# 11_LMS1_Power.net
KiCad netlist of a schematic drawn in Altium Designer
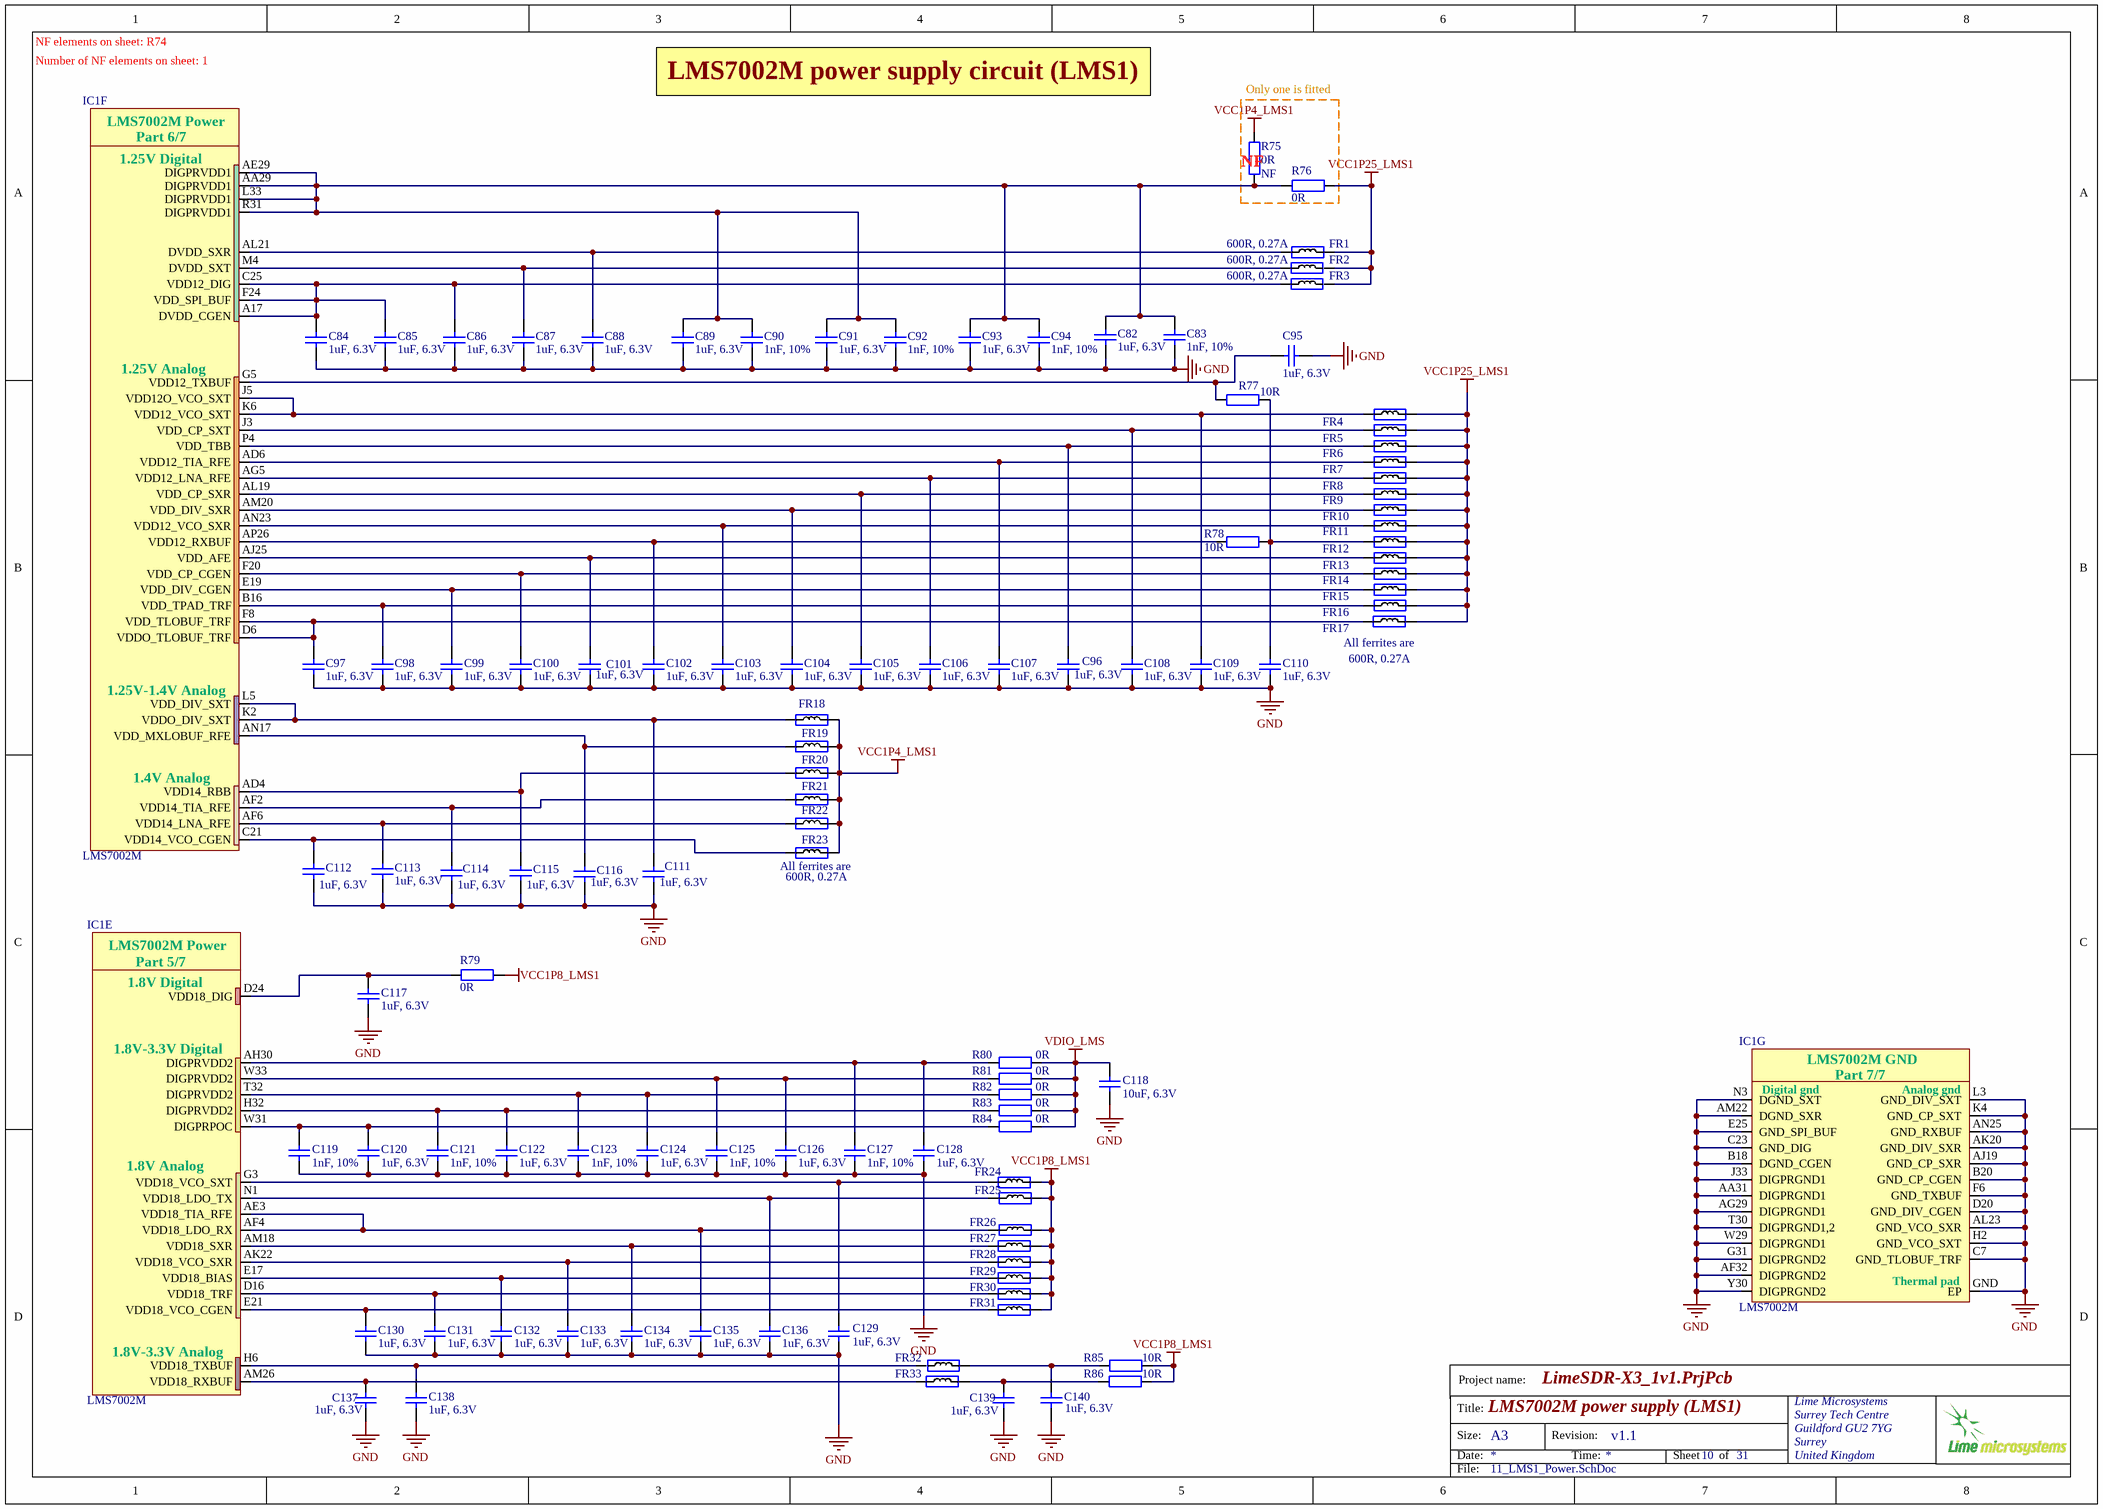
[diagram p0: 11_LMS1_Power.SchDoc]

(export (version "E")
  (design (tool "Eeschema 10.0.6"))
  (components
    (comp (ref "C82")
      (value "1uF, 6.3V")
      (footprint "CAP0201")
      (fields (field (name "TOLERANCE") "±20%") (field (name "MANUFACTURER") "TDK Corporation"))
      (libsource (lib "LimeMicroAltiumLib_schLib") (part "Cap_0402"))
    )
    (comp (ref "C83")
      (value "1nF, 10%")
      (footprint "CAP0201")
      (fields (field (name "TOLERANCE") "±10%") (field (name "MANUFACTURER") "TDK Corporation"))
      (libsource (lib "LimeMicroAltiumLib_schLib") (part "Cap_0402"))
    )
    (comp (ref "C84")
      (value "1uF, 6.3V")
      (footprint "CAP0201")
      (fields (field (name "TOLERANCE") "±20%") (field (name "MANUFACTURER") "TDK Corporation"))
      (libsource (lib "") (part "Cap_0402_1"))
    )
    (comp (ref "C85")
      (value "1uF, 6.3V")
      (footprint "CAP0201")
      (fields (field (name "TOLERANCE") "±20%") (field (name "MANUFACTURER") "TDK Corporation"))
      (libsource (lib "") (part "Cap_0402_1"))
    )
    (comp (ref "C86")
      (value "1uF, 6.3V")
      (footprint "CAP0201")
      (fields (field (name "TOLERANCE") "±20%") (field (name "MANUFACTURER") "TDK Corporation"))
      (libsource (lib "") (part "Cap_0402_1"))
    )
    (comp (ref "C87")
      (value "1uF, 6.3V")
      (footprint "CAP0201")
      (fields (field (name "TOLERANCE") "±20%") (field (name "MANUFACTURER") "TDK Corporation"))
      (libsource (lib "LimeMicroAltiumLib_schLib") (part "Cap_0402"))
    )
    (comp (ref "C88")
      (value "1uF, 6.3V")
      (footprint "CAP0201")
      (fields (field (name "TOLERANCE") "±20%") (field (name "MANUFACTURER") "TDK Corporation"))
      (libsource (lib "") (part "Cap_0402_1"))
    )
    (comp (ref "C89")
      (value "1uF, 6.3V")
      (footprint "CAP0201")
      (fields (field (name "TOLERANCE") "±20%") (field (name "MANUFACTURER") "TDK Corporation"))
      (libsource (lib "LimeMicroAltiumLib_schLib") (part "Cap_0402"))
    )
    (comp (ref "C90")
      (value "1nF, 10%")
      (footprint "CAP0201")
      (fields (field (name "TOLERANCE") "±10%") (field (name "MANUFACTURER") "TDK Corporation"))
      (libsource (lib "LimeMicroAltiumLib_schLib") (part "Cap_0402"))
    )
    (comp (ref "C91")
      (value "1uF, 6.3V")
      (footprint "CAP0201")
      (fields (field (name "TOLERANCE") "±20%") (field (name "MANUFACTURER") "TDK Corporation"))
      (libsource (lib "LimeMicroAltiumLib_schLib") (part "Cap_0402"))
    )
    (comp (ref "C92")
      (value "1nF, 10%")
      (footprint "CAP0201")
      (fields (field (name "TOLERANCE") "±10%") (field (name "MANUFACTURER") "TDK Corporation"))
      (libsource (lib "LimeMicroAltiumLib_schLib") (part "Cap_0402"))
    )
    (comp (ref "C93")
      (value "1uF, 6.3V")
      (footprint "CAP0201")
      (fields (field (name "TOLERANCE") "±20%") (field (name "MANUFACTURER") "TDK Corporation"))
      (libsource (lib "LimeMicroAltiumLib_schLib") (part "Cap_0402"))
    )
    (comp (ref "C94")
      (value "1nF, 10%")
      (footprint "CAP0201")
      (fields (field (name "TOLERANCE") "±10%") (field (name "MANUFACTURER") "TDK Corporation"))
      (libsource (lib "LimeMicroAltiumLib_schLib") (part "Cap_0402"))
    )
    (comp (ref "C95")
      (value "1uF, 6.3V")
      (footprint "CAP0201")
      (fields (field (name "TOLERANCE") "±20%") (field (name "MANUFACTURER") "TDK Corporation"))
      (libsource (lib "") (part "Cap_0402_4"))
    )
    (comp (ref "C96")
      (value "1uF, 6.3V")
      (footprint "CAP0201")
      (fields (field (name "TOLERANCE") "±20%") (field (name "MANUFACTURER") "TDK Corporation"))
      (libsource (lib "") (part "Cap_0402_1"))
    )
    (comp (ref "C97")
      (value "1uF, 6.3V")
      (footprint "CAP0201")
      (fields (field (name "TOLERANCE") "±20%") (field (name "MANUFACTURER") "TDK Corporation"))
      (libsource (lib "") (part "Cap_0402_1"))
    )
    (comp (ref "C98")
      (value "1uF, 6.3V")
      (footprint "CAP0201")
      (fields (field (name "TOLERANCE") "±20%") (field (name "MANUFACTURER") "TDK Corporation"))
      (libsource (lib "") (part "Cap_0402_1"))
    )
    (comp (ref "C99")
      (value "1uF, 6.3V")
      (footprint "CAP0201")
      (fields (field (name "TOLERANCE") "±20%") (field (name "MANUFACTURER") "TDK Corporation"))
      (libsource (lib "") (part "Cap_0402_1"))
    )
    (comp (ref "C100")
      (value "1uF, 6.3V")
      (footprint "CAP0201")
      (fields (field (name "TOLERANCE") "±20%") (field (name "MANUFACTURER") "TDK Corporation"))
      (libsource (lib "LimeMicroAltiumLib_schLib") (part "Cap_0402"))
    )
    (comp (ref "C101")
      (value "1uF, 6.3V")
      (footprint "CAP0201")
      (fields (field (name "TOLERANCE") "±20%") (field (name "MANUFACTURER") "TDK Corporation"))
      (libsource (lib "") (part "Cap_0402_1"))
    )
    (comp (ref "C102")
      (value "1uF, 6.3V")
      (footprint "CAP0201")
      (fields (field (name "TOLERANCE") "±20%") (field (name "MANUFACTURER") "TDK Corporation"))
      (libsource (lib "") (part "Cap_0402_1"))
    )
    (comp (ref "C103")
      (value "1uF, 6.3V")
      (footprint "CAP0201")
      (fields (field (name "TOLERANCE") "±20%") (field (name "MANUFACTURER") "TDK Corporation"))
      (libsource (lib "") (part "Cap_0402_1"))
    )
    (comp (ref "C104")
      (value "1uF, 6.3V")
      (footprint "CAP0201")
      (fields (field (name "TOLERANCE") "±20%") (field (name "MANUFACTURER") "TDK Corporation"))
      (libsource (lib "") (part "Cap_0402_1"))
    )
    (comp (ref "C105")
      (value "1uF, 6.3V")
      (footprint "CAP0201")
      (fields (field (name "TOLERANCE") "±20%") (field (name "MANUFACTURER") "TDK Corporation"))
      (libsource (lib "") (part "Cap_0402_1"))
    )
    (comp (ref "C106")
      (value "1uF, 6.3V")
      (footprint "CAP0201")
      (fields (field (name "TOLERANCE") "±20%") (field (name "MANUFACTURER") "TDK Corporation"))
      (libsource (lib "") (part "Cap_0402_1"))
    )
    (comp (ref "C107")
      (value "1uF, 6.3V")
      (footprint "CAP0201")
      (fields (field (name "TOLERANCE") "±20%") (field (name "MANUFACTURER") "TDK Corporation"))
      (libsource (lib "LimeMicroAltiumLib_schLib") (part "Cap_0402"))
    )
    (comp (ref "C108")
      (value "1uF, 6.3V")
      (footprint "CAP0201")
      (fields (field (name "TOLERANCE") "±20%") (field (name "MANUFACTURER") "TDK Corporation"))
      (libsource (lib "") (part "Cap_0402_1"))
    )
    (comp (ref "C109")
      (value "1uF, 6.3V")
      (footprint "CAP0201")
      (fields (field (name "TOLERANCE") "±20%") (field (name "MANUFACTURER") "TDK Corporation"))
      (libsource (lib "LimeMicroAltiumLib_schLib") (part "Cap_0402"))
    )
    (comp (ref "C110")
      (value "1uF, 6.3V")
      (footprint "CAP0201")
      (fields (field (name "TOLERANCE") "±20%") (field (name "MANUFACTURER") "TDK Corporation"))
      (libsource (lib "LimeMicroAltiumLib_schLib") (part "Cap_0402"))
    )
    (comp (ref "C111")
      (value "1uF, 6.3V")
      (footprint "CAP0201")
      (fields (field (name "TOLERANCE") "±20%") (field (name "MANUFACTURER") "TDK Corporation"))
      (libsource (lib "") (part "Cap_0402_1"))
    )
    (comp (ref "C112")
      (value "1uF, 6.3V")
      (footprint "CAP0201")
      (fields (field (name "TOLERANCE") "±20%") (field (name "MANUFACTURER") "TDK Corporation"))
      (libsource (lib "") (part "Cap_0402_1"))
    )
    (comp (ref "C113")
      (value "1uF, 6.3V")
      (footprint "CAP0201")
      (fields (field (name "TOLERANCE") "±20%") (field (name "MANUFACTURER") "TDK Corporation"))
      (libsource (lib "") (part "Cap_0402_1"))
    )
    (comp (ref "C114")
      (value "1uF, 6.3V")
      (footprint "CAP0201")
      (fields (field (name "TOLERANCE") "±20%") (field (name "MANUFACTURER") "TDK Corporation"))
      (libsource (lib "") (part "Cap_0402_3"))
    )
    (comp (ref "C115")
      (value "1uF, 6.3V")
      (footprint "CAP0201")
      (fields (field (name "TOLERANCE") "±20%") (field (name "MANUFACTURER") "TDK Corporation"))
      (libsource (lib "") (part "Cap_0402_3"))
    )
    (comp (ref "C116")
      (value "1uF, 6.3V")
      (footprint "CAP0201")
      (fields (field (name "TOLERANCE") "±20%") (field (name "MANUFACTURER") "TDK Corporation"))
      (libsource (lib "") (part "Cap_0402_1"))
    )
    (comp (ref "C117")
      (value "1uF, 6.3V")
      (footprint "CAP0201")
      (fields (field (name "TOLERANCE") "±20%") (field (name "MANUFACTURER") "TDK Corporation"))
      (libsource (lib "") (part "Cap_0402_2"))
    )
    (comp (ref "C118")
      (value "10uF, 6.3V")
      (footprint "CAP0603")
      (fields (field (name "TOLERANCE") "±20%") (field (name "MANUFACTURER") "Yageo"))
      (libsource (lib "LimeFPGAboard_schLib") (part "Cap_0603"))
    )
    (comp (ref "C119")
      (value "1nF, 10%")
      (footprint "CAP0201")
      (fields (field (name "TOLERANCE") "±10%") (field (name "MANUFACTURER") "TDK Corporation"))
      (libsource (lib "") (part "Cap_0402_2"))
    )
    (comp (ref "C120")
      (value "1uF, 6.3V")
      (footprint "CAP0201")
      (fields (field (name "TOLERANCE") "±20%") (field (name "MANUFACTURER") "TDK Corporation"))
      (libsource (lib "") (part "Cap_0402_2"))
    )
    (comp (ref "C121")
      (value "1nF, 10%")
      (footprint "CAP0201")
      (fields (field (name "TOLERANCE") "±10%") (field (name "MANUFACTURER") "TDK Corporation"))
      (libsource (lib "") (part "Cap_0402_2"))
    )
    (comp (ref "C122")
      (value "1uF, 6.3V")
      (footprint "CAP0201")
      (fields (field (name "TOLERANCE") "±20%") (field (name "MANUFACTURER") "TDK Corporation"))
      (libsource (lib "") (part "Cap_0402_2"))
    )
    (comp (ref "C123")
      (value "1nF, 10%")
      (footprint "CAP0201")
      (fields (field (name "TOLERANCE") "±10%") (field (name "MANUFACTURER") "TDK Corporation"))
      (libsource (lib "") (part "Cap_0402_2"))
    )
    (comp (ref "C124")
      (value "1uF, 6.3V")
      (footprint "CAP0201")
      (fields (field (name "TOLERANCE") "±20%") (field (name "MANUFACTURER") "TDK Corporation"))
      (libsource (lib "") (part "Cap_0402_2"))
    )
    (comp (ref "C125")
      (value "1nF, 10%")
      (footprint "CAP0201")
      (fields (field (name "TOLERANCE") "±10%") (field (name "MANUFACTURER") "TDK Corporation"))
      (libsource (lib "") (part "Cap_0402_2"))
    )
    (comp (ref "C126")
      (value "1uF, 6.3V")
      (footprint "CAP0201")
      (fields (field (name "TOLERANCE") "±20%") (field (name "MANUFACTURER") "TDK Corporation"))
      (libsource (lib "") (part "Cap_0402_2"))
    )
    (comp (ref "C127")
      (value "1nF, 10%")
      (footprint "CAP0201")
      (fields (field (name "TOLERANCE") "±10%") (field (name "MANUFACTURER") "TDK Corporation"))
      (libsource (lib "") (part "Cap_0402_2"))
    )
    (comp (ref "C128")
      (value "1uF, 6.3V")
      (footprint "CAP0201")
      (fields (field (name "TOLERANCE") "±20%") (field (name "MANUFACTURER") "TDK Corporation"))
      (libsource (lib "") (part "Cap_0402_2"))
    )
    (comp (ref "C129")
      (value "1uF, 6.3V")
      (footprint "CAP0201")
      (fields (field (name "TOLERANCE") "±20%") (field (name "MANUFACTURER") "TDK Corporation"))
      (libsource (lib "") (part "Cap_0402_2"))
    )
    (comp (ref "C130")
      (value "1uF, 6.3V")
      (footprint "CAP0201")
      (fields (field (name "TOLERANCE") "±20%") (field (name "MANUFACTURER") "TDK Corporation"))
      (libsource (lib "") (part "Cap_0402_2"))
    )
    (comp (ref "C131")
      (value "1uF, 6.3V")
      (footprint "CAP0201")
      (fields (field (name "TOLERANCE") "±20%") (field (name "MANUFACTURER") "TDK Corporation"))
      (libsource (lib "") (part "Cap_0402_2"))
    )
    (comp (ref "C132")
      (value "1uF, 6.3V")
      (footprint "CAP0201")
      (fields (field (name "TOLERANCE") "±20%") (field (name "MANUFACTURER") "TDK Corporation"))
      (libsource (lib "") (part "Cap_0402_2"))
    )
    (comp (ref "C133")
      (value "1uF, 6.3V")
      (footprint "CAP0201")
      (fields (field (name "TOLERANCE") "±20%") (field (name "MANUFACTURER") "TDK Corporation"))
      (libsource (lib "") (part "Cap_0402_2"))
    )
    (comp (ref "C134")
      (value "1uF, 6.3V")
      (footprint "CAP0201")
      (fields (field (name "TOLERANCE") "±20%") (field (name "MANUFACTURER") "TDK Corporation"))
      (libsource (lib "") (part "Cap_0402_2"))
    )
    (comp (ref "C135")
      (value "1uF, 6.3V")
      (footprint "CAP0201")
      (fields (field (name "TOLERANCE") "±20%") (field (name "MANUFACTURER") "TDK Corporation"))
      (libsource (lib "") (part "Cap_0402_2"))
    )
    (comp (ref "C136")
      (value "1uF, 6.3V")
      (footprint "CAP0201")
      (fields (field (name "TOLERANCE") "±20%") (field (name "MANUFACTURER") "TDK Corporation"))
      (libsource (lib "") (part "Cap_0402_2"))
    )
    (comp (ref "C137")
      (value "1uF, 6.3V")
      (footprint "CAP0201")
      (fields (field (name "TOLERANCE") "±20%") (field (name "MANUFACTURER") "TDK Corporation"))
      (libsource (lib "") (part "Cap_0402_2"))
    )
    (comp (ref "C138")
      (value "1uF, 6.3V")
      (footprint "CAP0201")
      (fields (field (name "TOLERANCE") "±20%") (field (name "MANUFACTURER") "TDK Corporation"))
      (libsource (lib "") (part "Cap_0402_2"))
    )
    (comp (ref "C139")
      (value "1uF, 6.3V")
      (footprint "CAP0201")
      (fields (field (name "TOLERANCE") "±20%") (field (name "MANUFACTURER") "TDK Corporation"))
      (libsource (lib "") (part "Cap_0402_2"))
    )
    (comp (ref "C140")
      (value "1uF, 6.3V")
      (footprint "CAP0201")
      (fields (field (name "TOLERANCE") "±20%") (field (name "MANUFACTURER") "TDK Corporation"))
      (libsource (lib "") (part "Cap_0402_2"))
    )
    (comp (ref "FR1")
      (value "600R, 0.27A")
      (footprint "RES0201")
      (fields (field (name "MANUFACTURER") "Taiyo Yuden"))
      (libsource (lib "LimeMicroAltiumLib_schLib") (part "Ferrite"))
    )
    (comp (ref "FR2")
      (value "600R, 0.27A")
      (footprint "RES0201")
      (fields (field (name "MANUFACTURER") "Taiyo Yuden"))
      (libsource (lib "") (part "Ferrite_1"))
    )
    (comp (ref "FR3")
      (value "600R, 0.27A")
      (footprint "RES0201")
      (fields (field (name "MANUFACTURER") "Taiyo Yuden"))
      (libsource (lib "") (part "Ferrite_1"))
    )
    (comp (ref "FR4")
      (value "600R, 0.27A")
      (footprint "RES0201")
      (fields (field (name "MANUFACTURER") "Taiyo Yuden"))
      (libsource (lib "LimeMicroAltiumLib_schLib") (part "Ferrite"))
    )
    (comp (ref "FR5")
      (value "600R, 0.27A")
      (footprint "RES0201")
      (fields (field (name "MANUFACTURER") "Taiyo Yuden"))
      (libsource (lib "LimeMicroAltiumLib_schLib") (part "Ferrite"))
    )
    (comp (ref "FR6")
      (value "600R, 0.27A")
      (footprint "RES0201")
      (fields (field (name "MANUFACTURER") "Taiyo Yuden"))
      (libsource (lib "LimeMicroAltiumLib_schLib") (part "Ferrite"))
    )
    (comp (ref "FR7")
      (value "600R, 0.27A")
      (footprint "RES0201")
      (fields (field (name "MANUFACTURER") "Taiyo Yuden"))
      (libsource (lib "LimeMicroAltiumLib_schLib") (part "Ferrite"))
    )
    (comp (ref "FR8")
      (value "600R, 0.27A")
      (footprint "RES0201")
      (fields (field (name "MANUFACTURER") "Taiyo Yuden"))
      (libsource (lib "LimeMicroAltiumLib_schLib") (part "Ferrite"))
    )
    (comp (ref "FR9")
      (value "600R, 0.27A")
      (footprint "RES0201")
      (fields (field (name "MANUFACTURER") "Taiyo Yuden"))
      (libsource (lib "LimeMicroAltiumLib_schLib") (part "Ferrite"))
    )
    (comp (ref "FR10")
      (value "600R, 0.27A")
      (footprint "RES0201")
      (fields (field (name "MANUFACTURER") "Taiyo Yuden"))
      (libsource (lib "LimeMicroAltiumLib_schLib") (part "Ferrite"))
    )
    (comp (ref "FR11")
      (value "600R, 0.27A")
      (footprint "RES0201")
      (fields (field (name "MANUFACTURER") "Taiyo Yuden"))
      (libsource (lib "LimeMicroAltiumLib_schLib") (part "Ferrite"))
    )
    (comp (ref "FR12")
      (value "600R, 0.27A")
      (footprint "RES0201")
      (fields (field (name "MANUFACTURER") "Taiyo Yuden"))
      (libsource (lib "LimeMicroAltiumLib_schLib") (part "Ferrite"))
    )
    (comp (ref "FR13")
      (value "600R, 0.27A")
      (footprint "RES0201")
      (fields (field (name "MANUFACTURER") "Taiyo Yuden"))
      (libsource (lib "LimeMicroAltiumLib_schLib") (part "Ferrite"))
    )
    (comp (ref "FR14")
      (value "600R, 0.27A")
      (footprint "RES0201")
      (fields (field (name "MANUFACTURER") "Taiyo Yuden"))
      (libsource (lib "LimeMicroAltiumLib_schLib") (part "Ferrite"))
    )
    (comp (ref "FR15")
      (value "600R, 0.27A")
      (footprint "RES0201")
      (fields (field (name "MANUFACTURER") "Taiyo Yuden"))
      (libsource (lib "LimeMicroAltiumLib_schLib") (part "Ferrite"))
    )
    (comp (ref "FR16")
      (value "600R, 0.27A")
      (footprint "RES0201")
      (fields (field (name "MANUFACTURER") "Taiyo Yuden"))
      (libsource (lib "LimeMicroAltiumLib_schLib") (part "Ferrite"))
    )
    (comp (ref "FR17")
      (value "600R, 0.27A")
      (footprint "RES0201")
      (fields (field (name "MANUFACTURER") "Taiyo Yuden"))
      (libsource (lib "") (part "Ferrite_1"))
    )
    (comp (ref "FR18")
      (value "600R, 0.27A")
      (footprint "RES0201")
      (fields (field (name "MANUFACTURER") "Taiyo Yuden"))
      (libsource (lib "") (part "Ferrite_1"))
    )
    (comp (ref "FR19")
      (value "600R, 0.27A")
      (footprint "RES0201")
      (fields (field (name "MANUFACTURER") "Taiyo Yuden"))
      (libsource (lib "") (part "Ferrite_1"))
    )
    (comp (ref "FR20")
      (value "600R, 0.27A")
      (footprint "RES0201")
      (fields (field (name "MANUFACTURER") "Taiyo Yuden"))
      (libsource (lib "") (part "Ferrite_1"))
    )
    (comp (ref "FR21")
      (value "600R, 0.27A")
      (footprint "RES0201")
      (fields (field (name "MANUFACTURER") "Taiyo Yuden"))
      (libsource (lib "") (part "Ferrite_1"))
    )
    (comp (ref "FR22")
      (value "600R, 0.27A")
      (footprint "RES0201")
      (fields (field (name "MANUFACTURER") "Taiyo Yuden"))
      (libsource (lib "") (part "Ferrite_1"))
    )
    (comp (ref "FR23")
      (value "600R, 0.27A")
      (footprint "RES0201")
      (fields (field (name "MANUFACTURER") "Taiyo Yuden"))
      (libsource (lib "") (part "Ferrite_1"))
    )
    (comp (ref "FR24")
      (value "600R, 0.27A")
      (footprint "RES0201")
      (fields (field (name "MANUFACTURER") "Taiyo Yuden"))
      (libsource (lib "") (part "Ferrite_1"))
    )
    (comp (ref "FR25")
      (value "600R, 0.27A")
      (footprint "RES0201")
      (fields (field (name "MANUFACTURER") "Taiyo Yuden"))
      (libsource (lib "") (part "Ferrite_2"))
    )
    (comp (ref "FR26")
      (value "600R, 0.27A")
      (footprint "RES0201")
      (fields (field (name "MANUFACTURER") "Taiyo Yuden"))
      (libsource (lib "") (part "Ferrite_2"))
    )
    (comp (ref "FR27")
      (value "600R, 0.27A")
      (footprint "RES0201")
      (fields (field (name "MANUFACTURER") "Taiyo Yuden"))
      (libsource (lib "") (part "Ferrite_1"))
    )
    (comp (ref "FR28")
      (value "600R, 0.27A")
      (footprint "RES0201")
      (fields (field (name "MANUFACTURER") "Taiyo Yuden"))
      (libsource (lib "") (part "Ferrite_1"))
    )
    (comp (ref "FR29")
      (value "600R, 0.27A")
      (footprint "RES0201")
      (fields (field (name "MANUFACTURER") "Taiyo Yuden"))
      (libsource (lib "") (part "Ferrite_1"))
    )
    (comp (ref "FR30")
      (value "600R, 0.27A")
      (footprint "RES0201")
      (fields (field (name "MANUFACTURER") "Taiyo Yuden"))
      (libsource (lib "") (part "Ferrite_1"))
    )
    (comp (ref "FR31")
      (value "600R, 0.27A")
      (footprint "RES0201")
      (fields (field (name "MANUFACTURER") "Taiyo Yuden"))
      (libsource (lib "") (part "Ferrite_1"))
    )
    (comp (ref "FR32")
      (value "600R, 0.27A")
      (footprint "RES0201")
      (fields (field (name "MANUFACTURER") "Taiyo Yuden"))
      (libsource (lib "") (part "Ferrite_2"))
    )
    (comp (ref "FR33")
      (value "600R, 0.27A")
      (footprint "RES0201")
      (fields (field (name "MANUFACTURER") "Taiyo Yuden"))
      (libsource (lib "") (part "Ferrite_1"))
    )
    (comp (ref "IC1")
      (value "LMS7002M")
      (footprint "LMS7002M_v5")
      (description "Schematic symbol revision 4. Default footprint - 0.31mm pad")
      (fields (field (name "MANUFACTURER") "Lime Microsystems"))
      (libsource (lib "LimeMicroAltiumLib_schLib_r04") (part "LMS7002Mr4"))
    )
    (comp (ref "R75")
      (value "0R")
      (footprint "RES0402")
      (fields
        (field (name "ASSEMBLY INFO") "NF")
        (field (name "MANUFACTURER") "Yageo")
        (field (name "TOLERANCE") "Jumper")
      )
      (libsource (lib "LimeMicroAltiumLib_schLib") (part "Res_0402"))
    )
    (comp (ref "R76")
      (value "0R")
      (footprint "RES0402")
      (fields (field (name "MANUFACTURER") "Yageo") (field (name "TOLERANCE") "Jumper"))
      (libsource (lib "") (part "Res_0402_1"))
    )
    (comp (ref "R77")
      (value "10R")
      (footprint "RES0201")
      (fields
        (field (name "MANUFACTURER") "Panasonic Electronic Components")
        (field (name "TOLERANCE") "±1%")
      )
      (libsource (lib "LimeMicroAltiumLib_schLib") (part "Res_0402"))
    )
    (comp (ref "R78")
      (value "10R")
      (footprint "RES0201")
      (fields
        (field (name "MANUFACTURER") "Panasonic Electronic Components")
        (field (name "TOLERANCE") "±1%")
      )
      (libsource (lib "LimeMicroAltiumLib_schLib") (part "Res_0402"))
    )
    (comp (ref "R79")
      (value "0R")
      (footprint "RES0201")
      (fields (field (name "MANUFACTURER") "Rohm Semiconductor") (field (name "TOLERANCE") "Jumper"))
      (libsource (lib "LimeMicroAltiumLib_schLib") (part "Res_0402"))
    )
    (comp (ref "R80")
      (value "0R")
      (footprint "RES0402")
      (fields (field (name "MANUFACTURER") "Yageo") (field (name "TOLERANCE") "Jumper"))
      (libsource (lib "LimeMicroAltiumLib_schLib") (part "Res_0402"))
    )
    (comp (ref "R81")
      (value "0R")
      (footprint "RES0402")
      (fields (field (name "MANUFACTURER") "Yageo") (field (name "TOLERANCE") "Jumper"))
      (libsource (lib "LimeMicroAltiumLib_schLib") (part "Res_0402"))
    )
    (comp (ref "R82")
      (value "0R")
      (footprint "RES0402")
      (fields (field (name "MANUFACTURER") "Yageo") (field (name "TOLERANCE") "Jumper"))
      (libsource (lib "LimeMicroAltiumLib_schLib") (part "Res_0402"))
    )
    (comp (ref "R83")
      (value "0R")
      (footprint "RES0402")
      (fields (field (name "MANUFACTURER") "Yageo") (field (name "TOLERANCE") "Jumper"))
      (libsource (lib "LimeMicroAltiumLib_schLib") (part "Res_0402"))
    )
    (comp (ref "R84")
      (value "0R")
      (footprint "RES0402")
      (fields (field (name "MANUFACTURER") "Yageo") (field (name "TOLERANCE") "Jumper"))
      (libsource (lib "LimeMicroAltiumLib_schLib") (part "Res_0402"))
    )
    (comp (ref "R85")
      (value "10R")
      (footprint "RES0201")
      (fields
        (field (name "MANUFACTURER") "Panasonic Electronic Components")
        (field (name "TOLERANCE") "±1%")
      )
      (libsource (lib "LimeMicroAltiumLib_schLib") (part "Res_0402"))
    )
    (comp (ref "R86")
      (value "10R")
      (footprint "RES0201")
      (fields
        (field (name "MANUFACTURER") "Panasonic Electronic Components")
        (field (name "TOLERANCE") "±1%")
      )
      (libsource (lib "LimeMicroAltiumLib_schLib") (part "Res_0402"))
    )
  )
  (nets
    (net (code "1") (name "GND") (class "Default")
      (node (ref "C100") (pin "1") (pinfunction "1_1") (pintype "passive"))
      (node (ref "C101") (pin "2") (pinfunction "2_2") (pintype "passive"))
      (node (ref "C102") (pin "2") (pinfunction "2_2") (pintype "passive"))
      (node (ref "C103") (pin "2") (pinfunction "2_2") (pintype "passive"))
      (node (ref "C104") (pin "2") (pinfunction "2_2") (pintype "passive"))
      (node (ref "C105") (pin "2") (pinfunction "2_2") (pintype "passive"))
      (node (ref "C106") (pin "2") (pinfunction "2_2") (pintype "passive"))
      (node (ref "C107") (pin "1") (pinfunction "1_1") (pintype "passive"))
      (node (ref "C108") (pin "2") (pinfunction "2_2") (pintype "passive"))
      (node (ref "C109") (pin "1") (pinfunction "1_1") (pintype "passive"))
      (node (ref "C110") (pin "1") (pinfunction "1_1") (pintype "passive"))
      (node (ref "C111") (pin "2") (pinfunction "2_2") (pintype "passive"))
      (node (ref "C112") (pin "2") (pinfunction "2_2") (pintype "passive"))
      (node (ref "C113") (pin "2") (pinfunction "2_2") (pintype "passive"))
      (node (ref "C114") (pin "2") (pinfunction "2_2") (pintype "passive"))
      (node (ref "C115") (pin "2") (pinfunction "2_2") (pintype "passive"))
      (node (ref "C116") (pin "2") (pinfunction "2_2") (pintype "passive"))
      (node (ref "C117") (pin "2") (pinfunction "2_2") (pintype "passive"))
      (node (ref "C118") (pin "1") (pinfunction "1_1") (pintype "passive"))
      (node (ref "C119") (pin "2") (pinfunction "2_2") (pintype "passive"))
      (node (ref "C120") (pin "2") (pinfunction "2_2") (pintype "passive"))
      (node (ref "C121") (pin "2") (pinfunction "2_2") (pintype "passive"))
      (node (ref "C122") (pin "2") (pinfunction "2_2") (pintype "passive"))
      (node (ref "C123") (pin "2") (pinfunction "2_2") (pintype "passive"))
      (node (ref "C124") (pin "2") (pinfunction "2_2") (pintype "passive"))
      (node (ref "C125") (pin "2") (pinfunction "2_2") (pintype "passive"))
      (node (ref "C126") (pin "2") (pinfunction "2_2") (pintype "passive"))
      (node (ref "C127") (pin "2") (pinfunction "2_2") (pintype "passive"))
      (node (ref "C128") (pin "2") (pinfunction "2_2") (pintype "passive"))
      (node (ref "C129") (pin "2") (pinfunction "2_2") (pintype "passive"))
      (node (ref "C130") (pin "2") (pinfunction "2_2") (pintype "passive"))
      (node (ref "C131") (pin "2") (pinfunction "2_2") (pintype "passive"))
      (node (ref "C132") (pin "2") (pinfunction "2_2") (pintype "passive"))
      (node (ref "C133") (pin "2") (pinfunction "2_2") (pintype "passive"))
      (node (ref "C134") (pin "2") (pinfunction "2_2") (pintype "passive"))
      (node (ref "C135") (pin "2") (pinfunction "2_2") (pintype "passive"))
      (node (ref "C136") (pin "2") (pinfunction "2_2") (pintype "passive"))
      (node (ref "C137") (pin "2") (pinfunction "2_2") (pintype "passive"))
      (node (ref "C138") (pin "2") (pinfunction "2_2") (pintype "passive"))
      (node (ref "C139") (pin "2") (pinfunction "2_2") (pintype "passive"))
      (node (ref "C140") (pin "2") (pinfunction "2_2") (pintype "passive"))
      (node (ref "C82") (pin "2") (pinfunction "2_2") (pintype "passive"))
      (node (ref "C83") (pin "2") (pinfunction "2_2") (pintype "passive"))
      (node (ref "C84") (pin "2") (pinfunction "2_2") (pintype "passive"))
      (node (ref "C85") (pin "2") (pinfunction "2_2") (pintype "passive"))
      (node (ref "C86") (pin "2") (pinfunction "2_2") (pintype "passive"))
      (node (ref "C87") (pin "1") (pinfunction "1_1") (pintype "passive"))
      (node (ref "C88") (pin "2") (pinfunction "2_2") (pintype "passive"))
      (node (ref "C89") (pin "2") (pinfunction "2_2") (pintype "passive"))
      (node (ref "C90") (pin "2") (pinfunction "2_2") (pintype "passive"))
      (node (ref "C91") (pin "2") (pinfunction "2_2") (pintype "passive"))
      (node (ref "C92") (pin "2") (pinfunction "2_2") (pintype "passive"))
      (node (ref "C93") (pin "2") (pinfunction "2_2") (pintype "passive"))
      (node (ref "C94") (pin "2") (pinfunction "2_2") (pintype "passive"))
      (node (ref "C95") (pin "2") (pinfunction "2_2") (pintype "passive"))
      (node (ref "C96") (pin "2") (pinfunction "2_2") (pintype "passive"))
      (node (ref "C97") (pin "2") (pinfunction "2_2") (pintype "passive"))
      (node (ref "C98") (pin "2") (pinfunction "2_2") (pintype "passive"))
      (node (ref "C99") (pin "2") (pinfunction "2_2") (pintype "passive"))
      (node (ref "IC1") (pin "AA31") (pinfunction "DIGPRGND1_AA31") (pintype "passive"))
      (node (ref "IC1") (pin "AF32") (pinfunction "DIGPRGND2_AF32") (pintype "passive"))
      (node (ref "IC1") (pin "AG29") (pinfunction "DIGPRGND1_AG29") (pintype "passive"))
      (node (ref "IC1") (pin "AJ19") (pinfunction "GND_CP_SXR_AJ19") (pintype "passive"))
      (node (ref "IC1") (pin "AK20") (pinfunction "GND_DIV_SXR_AK20") (pintype "passive"))
      (node (ref "IC1") (pin "AL23") (pinfunction "GND_VCO_SXR_AL23") (pintype "passive"))
      (node (ref "IC1") (pin "AM22") (pinfunction "DGND_SXR_AM22") (pintype "passive"))
      (node (ref "IC1") (pin "AN25") (pinfunction "GND_RXBUF_AN25") (pintype "passive"))
      (node (ref "IC1") (pin "B18") (pinfunction "DGND_CGEN_B18") (pintype "passive"))
      (node (ref "IC1") (pin "B20") (pinfunction "GND_CP_CGEN_B20") (pintype "passive"))
      (node (ref "IC1") (pin "C23") (pinfunction "GND_DIG_C23") (pintype "passive"))
      (node (ref "IC1") (pin "C7") (pinfunction "GND_TLOBUF_TRF_C7") (pintype "passive"))
      (node (ref "IC1") (pin "D20") (pinfunction "GND_DIV_CGEN_D20") (pintype "passive"))
      (node (ref "IC1") (pin "E25") (pinfunction "GND_SPI_BUF_E25") (pintype "passive"))
      (node (ref "IC1") (pin "F6") (pinfunction "GND_TXBUF_F6") (pintype "passive"))
      (node (ref "IC1") (pin "G31") (pinfunction "DIGPRGND2_G31") (pintype "passive"))
      (node (ref "IC1") (pin "GND") (pinfunction "EP_GND") (pintype "passive"))
      (node (ref "IC1") (pin "H2") (pinfunction "GND_VCO_SXT_H2") (pintype "passive"))
      (node (ref "IC1") (pin "J33") (pinfunction "DIGPRGND1_J33") (pintype "passive"))
      (node (ref "IC1") (pin "K4") (pinfunction "GND_CP_SXT_K4") (pintype "passive"))
      (node (ref "IC1") (pin "L3") (pinfunction "GND_DIV_SXT_L3") (pintype "passive"))
      (node (ref "IC1") (pin "N3") (pinfunction "DGND_SXT_N3") (pintype "passive"))
      (node (ref "IC1") (pin "T30") (pinfunction "DIGPRGND1,2_T30") (pintype "passive"))
      (node (ref "IC1") (pin "W29") (pinfunction "DIGPRGND1_W29") (pintype "passive"))
      (node (ref "IC1") (pin "Y30") (pinfunction "DIGPRGND2_Y30") (pintype "passive"))
    )
    (net (code "2") (name "Net-(C82-Pad1)") (class "Default")
      (node (ref "C82") (pin "1") (pinfunction "1_1") (pintype "passive"))
      (node (ref "C83") (pin "1") (pinfunction "1_1") (pintype "passive"))
      (node (ref "C89") (pin "1") (pinfunction "1_1") (pintype "passive"))
      (node (ref "C90") (pin "1") (pinfunction "1_1") (pintype "passive"))
      (node (ref "C91") (pin "1") (pinfunction "1_1") (pintype "passive"))
      (node (ref "C92") (pin "1") (pinfunction "1_1") (pintype "passive"))
      (node (ref "C93") (pin "1") (pinfunction "1_1") (pintype "passive"))
      (node (ref "C94") (pin "1") (pinfunction "1_1") (pintype "passive"))
      (node (ref "IC1") (pin "AA29") (pinfunction "DIGPRVDD1_AA29") (pintype "power_in"))
      (node (ref "IC1") (pin "AE29") (pinfunction "DIGPRVDD1_AE29") (pintype "power_in"))
      (node (ref "IC1") (pin "L33") (pinfunction "DIGPRVDD1_L33") (pintype "power_in"))
      (node (ref "IC1") (pin "R31") (pinfunction "DIGPRVDD1_R31") (pintype "power_in"))
      (node (ref "R75") (pin "2") (pinfunction "2_2") (pintype "passive"))
      (node (ref "R76") (pin "2") (pinfunction "2_2") (pintype "passive"))
    )
    (net (code "3") (name "Net-(C110-Pad2)") (class "Default")
      (node (ref "C110") (pin "2") (pinfunction "2_2") (pintype "passive"))
      (node (ref "FR12") (pin "1") (pinfunction "1_1") (pintype "passive"))
      (node (ref "R77") (pin "2") (pinfunction "2_2") (pintype "passive"))
      (node (ref "R78") (pin "2") (pinfunction "2_2") (pintype "passive"))
    )
    (net (code "4") (name "Net-(C121-Pad1)") (class "Default")
      (node (ref "C121") (pin "1") (pinfunction "1_1") (pintype "passive"))
      (node (ref "C122") (pin "1") (pinfunction "1_1") (pintype "passive"))
      (node (ref "IC1") (pin "H32") (pinfunction "DIGPRVDD2_H32") (pintype "power_in"))
      (node (ref "R83") (pin "2") (pinfunction "2_2") (pintype "passive"))
    )
    (net (code "5") (name "Net-(C123-Pad1)") (class "Default")
      (node (ref "C123") (pin "1") (pinfunction "1_1") (pintype "passive"))
      (node (ref "C124") (pin "1") (pinfunction "1_1") (pintype "passive"))
      (node (ref "IC1") (pin "T32") (pinfunction "DIGPRVDD2_T32") (pintype "power_in"))
      (node (ref "R82") (pin "2") (pinfunction "2_2") (pintype "passive"))
    )
    (net (code "6") (name "Net-(C125-Pad1)") (class "Default")
      (node (ref "C125") (pin "1") (pinfunction "1_1") (pintype "passive"))
      (node (ref "C126") (pin "1") (pinfunction "1_1") (pintype "passive"))
      (node (ref "IC1") (pin "W33") (pinfunction "DIGPRVDD2_W33") (pintype "power_in"))
      (node (ref "R81") (pin "2") (pinfunction "2_2") (pintype "passive"))
    )
    (net (code "7") (name "Net-(C127-Pad1)") (class "Default")
      (node (ref "C127") (pin "1") (pinfunction "1_1") (pintype "passive"))
      (node (ref "C128") (pin "1") (pinfunction "1_1") (pintype "passive"))
      (node (ref "IC1") (pin "AH30") (pinfunction "DIGPRVDD2_AH30") (pintype "power_in"))
      (node (ref "R80") (pin "2") (pinfunction "2_2") (pintype "passive"))
    )
    (net (code "8") (name "Net-(C139-Pad1)") (class "Default")
      (node (ref "C139") (pin "1") (pinfunction "1_1") (pintype "passive"))
      (node (ref "FR33") (pin "2") (pinfunction "2_2") (pintype "passive"))
      (node (ref "R86") (pin "2") (pinfunction "2_2") (pintype "passive"))
    )
    (net (code "9") (name "Net-(C140-Pad1)") (class "Default")
      (node (ref "C140") (pin "1") (pinfunction "1_1") (pintype "passive"))
      (node (ref "FR32") (pin "1") (pinfunction "1_1") (pintype "passive"))
      (node (ref "R85") (pin "1") (pinfunction "1_1") (pintype "passive"))
    )
    (net (code "10") (name "Net-(IC1E-DIGPRPOC)") (class "Default")
      (node (ref "C119") (pin "1") (pinfunction "1_1") (pintype "passive"))
      (node (ref "C120") (pin "1") (pinfunction "1_1") (pintype "passive"))
      (node (ref "IC1") (pin "W31") (pinfunction "DIGPRPOC_W31") (pintype "power_in"))
      (node (ref "R84") (pin "2") (pinfunction "2_2") (pintype "passive"))
    )
    (net (code "11") (name "Net-(IC1E-VDD18_BIAS)") (class "Default")
      (node (ref "C132") (pin "1") (pinfunction "1_1") (pintype "passive"))
      (node (ref "FR29") (pin "1") (pinfunction "1_1") (pintype "passive"))
      (node (ref "IC1") (pin "E17") (pinfunction "VDD18_BIAS_E17") (pintype "power_in"))
    )
    (net (code "12") (name "Net-(IC1E-VDD18_DIG)") (class "Default")
      (node (ref "C117") (pin "1") (pinfunction "1_1") (pintype "passive"))
      (node (ref "IC1") (pin "D24") (pinfunction "VDD18_DIG_D24") (pintype "power_in"))
      (node (ref "R79") (pin "1") (pinfunction "1_1") (pintype "passive"))
    )
    (net (code "13") (name "Net-(IC1E-VDD18_LDO_RX)") (class "Default")
      (node (ref "C135") (pin "1") (pinfunction "1_1") (pintype "passive"))
      (node (ref "FR26") (pin "2") (pinfunction "2_2") (pintype "passive"))
      (node (ref "IC1") (pin "AE3") (pinfunction "VDD18_TIA_RFE_AE3") (pintype "power_in"))
      (node (ref "IC1") (pin "AF4") (pinfunction "VDD18_LDO_RX_AF4") (pintype "power_in"))
    )
    (net (code "14") (name "Net-(IC1E-VDD18_LDO_TX)") (class "Default")
      (node (ref "C136") (pin "1") (pinfunction "1_1") (pintype "passive"))
      (node (ref "FR25") (pin "2") (pinfunction "2_2") (pintype "passive"))
      (node (ref "IC1") (pin "N1") (pinfunction "VDD18_LDO_TX_N1") (pintype "power_in"))
    )
    (net (code "15") (name "Net-(IC1E-VDD18_RXBUF)") (class "Default")
      (node (ref "C137") (pin "1") (pinfunction "1_1") (pintype "passive"))
      (node (ref "FR33") (pin "1") (pinfunction "1_1") (pintype "passive"))
      (node (ref "IC1") (pin "AM26") (pinfunction "VDD18_RXBUF_AM26") (pintype "power_in"))
    )
    (net (code "16") (name "Net-(IC1E-VDD18_SXR)") (class "Default")
      (node (ref "C134") (pin "1") (pinfunction "1_1") (pintype "passive"))
      (node (ref "FR27") (pin "1") (pinfunction "1_1") (pintype "passive"))
      (node (ref "IC1") (pin "AM18") (pinfunction "VDD18_SXR_AM18") (pintype "power_in"))
    )
    (net (code "17") (name "Net-(IC1E-VDD18_TRF)") (class "Default")
      (node (ref "C131") (pin "1") (pinfunction "1_1") (pintype "passive"))
      (node (ref "FR30") (pin "1") (pinfunction "1_1") (pintype "passive"))
      (node (ref "IC1") (pin "D16") (pinfunction "VDD18_TRF_D16") (pintype "power_in"))
    )
    (net (code "18") (name "Net-(IC1E-VDD18_TXBUF)") (class "Default")
      (node (ref "C138") (pin "1") (pinfunction "1_1") (pintype "passive"))
      (node (ref "FR32") (pin "2") (pinfunction "2_2") (pintype "passive"))
      (node (ref "IC1") (pin "H6") (pinfunction "VDD18_TXBUF_H6") (pintype "power_in"))
    )
    (net (code "19") (name "Net-(IC1E-VDD18_VCO_CGEN)") (class "Default")
      (node (ref "C130") (pin "1") (pinfunction "1_1") (pintype "passive"))
      (node (ref "FR31") (pin "1") (pinfunction "1_1") (pintype "passive"))
      (node (ref "IC1") (pin "E21") (pinfunction "VDD18_VCO_CGEN_E21") (pintype "power_in"))
    )
    (net (code "20") (name "Net-(IC1E-VDD18_VCO_SXR)") (class "Default")
      (node (ref "C133") (pin "1") (pinfunction "1_1") (pintype "passive"))
      (node (ref "FR28") (pin "1") (pinfunction "1_1") (pintype "passive"))
      (node (ref "IC1") (pin "AK22") (pinfunction "VDD18_VCO_SXR_AK22") (pintype "power_in"))
    )
    (net (code "21") (name "Net-(IC1E-VDD18_VCO_SXT)") (class "Default")
      (node (ref "C129") (pin "1") (pinfunction "1_1") (pintype "passive"))
      (node (ref "FR24") (pin "1") (pinfunction "1_1") (pintype "passive"))
      (node (ref "IC1") (pin "G3") (pinfunction "VDD18_VCO_SXT_G3") (pintype "power_in"))
    )
    (net (code "22") (name "Net-(IC1F-DVDD_CGEN)") (class "Default")
      (node (ref "C84") (pin "1") (pinfunction "1_1") (pintype "passive"))
      (node (ref "C85") (pin "1") (pinfunction "1_1") (pintype "passive"))
      (node (ref "C86") (pin "1") (pinfunction "1_1") (pintype "passive"))
      (node (ref "FR3") (pin "1") (pinfunction "1_1") (pintype "passive"))
      (node (ref "IC1") (pin "A17") (pinfunction "DVDD_CGEN_A17") (pintype "power_in"))
      (node (ref "IC1") (pin "C25") (pinfunction "VDD12_DIG_C25") (pintype "power_in"))
      (node (ref "IC1") (pin "F24") (pinfunction "VDD_SPI_BUF_F24") (pintype "power_in"))
    )
    (net (code "23") (name "Net-(IC1F-DVDD_SXR)") (class "Default")
      (node (ref "C88") (pin "1") (pinfunction "1_1") (pintype "passive"))
      (node (ref "FR1") (pin "1") (pinfunction "1_1") (pintype "passive"))
      (node (ref "IC1") (pin "AL21") (pinfunction "DVDD_SXR_AL21") (pintype "power_in"))
    )
    (net (code "24") (name "Net-(IC1F-DVDD_SXT)") (class "Default")
      (node (ref "C87") (pin "2") (pinfunction "2_2") (pintype "passive"))
      (node (ref "FR2") (pin "1") (pinfunction "1_1") (pintype "passive"))
      (node (ref "IC1") (pin "M4") (pinfunction "DVDD_SXT_M4") (pintype "power_in"))
    )
    (net (code "25") (name "Net-(IC1F-VDD12O_VCO_SXT)") (class "Default")
      (node (ref "C109") (pin "2") (pinfunction "2_2") (pintype "passive"))
      (node (ref "FR4") (pin "1") (pinfunction "1_1") (pintype "passive"))
      (node (ref "IC1") (pin "J5") (pinfunction "VDD12O_VCO_SXT_J5") (pintype "power_in"))
      (node (ref "IC1") (pin "K6") (pinfunction "VDD12_VCO_SXT_K6") (pintype "power_in"))
    )
    (net (code "26") (name "Net-(IC1F-VDD12_LNA_RFE)") (class "Default")
      (node (ref "C106") (pin "1") (pinfunction "1_1") (pintype "passive"))
      (node (ref "FR8") (pin "1") (pinfunction "1_1") (pintype "passive"))
      (node (ref "IC1") (pin "AG5") (pinfunction "VDD12_LNA_RFE_AG5") (pintype "power_in"))
    )
    (net (code "27") (name "Net-(IC1F-VDD12_RXBUF)") (class "Default")
      (node (ref "C102") (pin "1") (pinfunction "1_1") (pintype "passive"))
      (node (ref "IC1") (pin "AP26") (pinfunction "VDD12_RXBUF_AP26") (pintype "power_in"))
      (node (ref "R78") (pin "1") (pinfunction "1_1") (pintype "passive"))
    )
    (net (code "28") (name "Net-(IC1F-VDD12_TIA_RFE)") (class "Default")
      (node (ref "C107") (pin "2") (pinfunction "2_2") (pintype "passive"))
      (node (ref "FR7") (pin "1") (pinfunction "1_1") (pintype "passive"))
      (node (ref "IC1") (pin "AD6") (pinfunction "VDD12_TIA_RFE_AD6") (pintype "power_in"))
    )
    (net (code "29") (name "Net-(IC1F-VDD12_TXBUF)") (class "Default")
      (node (ref "C95") (pin "1") (pinfunction "1_1") (pintype "passive"))
      (node (ref "IC1") (pin "G5") (pinfunction "VDD12_TXBUF_G5") (pintype "power_in"))
      (node (ref "R77") (pin "1") (pinfunction "1_1") (pintype "passive"))
    )
    (net (code "30") (name "Net-(IC1F-VDD12_VCO_SXR)") (class "Default")
      (node (ref "C103") (pin "1") (pinfunction "1_1") (pintype "passive"))
      (node (ref "FR11") (pin "1") (pinfunction "1_1") (pintype "passive"))
      (node (ref "IC1") (pin "AN23") (pinfunction "VDD12_VCO_SXR_AN23") (pintype "power_in"))
    )
    (net (code "31") (name "Net-(IC1F-VDD14_LNA_RFE)") (class "Default")
      (node (ref "C113") (pin "1") (pinfunction "1_1") (pintype "passive"))
      (node (ref "FR22") (pin "1") (pinfunction "1_1") (pintype "passive"))
      (node (ref "IC1") (pin "AF6") (pinfunction "VDD14_LNA_RFE_AF6") (pintype "power_in"))
    )
    (net (code "32") (name "Net-(IC1F-VDD14_RBB)") (class "Default")
      (node (ref "C115") (pin "1") (pinfunction "1_1") (pintype "passive"))
      (node (ref "FR20") (pin "1") (pinfunction "1_1") (pintype "passive"))
      (node (ref "IC1") (pin "AD4") (pinfunction "VDD14_RBB_AD4") (pintype "power_in"))
    )
    (net (code "33") (name "Net-(IC1F-VDD14_TIA_RFE)") (class "Default")
      (node (ref "C114") (pin "1") (pinfunction "1_1") (pintype "passive"))
      (node (ref "FR21") (pin "1") (pinfunction "1_1") (pintype "passive"))
      (node (ref "IC1") (pin "AF2") (pinfunction "VDD14_TIA_RFE_AF2") (pintype "power_in"))
    )
    (net (code "34") (name "Net-(IC1F-VDD14_VCO_CGEN)") (class "Default")
      (node (ref "C112") (pin "1") (pinfunction "1_1") (pintype "passive"))
      (node (ref "FR23") (pin "1") (pinfunction "1_1") (pintype "passive"))
      (node (ref "IC1") (pin "C21") (pinfunction "VDD14_VCO_CGEN_C21") (pintype "power_in"))
    )
    (net (code "35") (name "Net-(IC1F-VDDO_DIV_SXT)") (class "Default")
      (node (ref "C111") (pin "1") (pinfunction "1_1") (pintype "passive"))
      (node (ref "FR18") (pin "1") (pinfunction "1_1") (pintype "passive"))
      (node (ref "IC1") (pin "K2") (pinfunction "VDDO_DIV_SXT_K2") (pintype "power_in"))
      (node (ref "IC1") (pin "L5") (pinfunction "VDD_DIV_SXT_L5") (pintype "power_in"))
    )
    (net (code "36") (name "Net-(IC1F-VDDO_TLOBUF_TRF)") (class "Default")
      (node (ref "C97") (pin "1") (pinfunction "1_1") (pintype "passive"))
      (node (ref "FR17") (pin "1") (pinfunction "1_1") (pintype "passive"))
      (node (ref "IC1") (pin "D6") (pinfunction "VDDO_TLOBUF_TRF_D6") (pintype "power_in"))
      (node (ref "IC1") (pin "F8") (pinfunction "VDD_TLOBUF_TRF_F8") (pintype "power_in"))
    )
    (net (code "37") (name "Net-(IC1F-VDD_AFE)") (class "Default")
      (node (ref "C101") (pin "1") (pinfunction "1_1") (pintype "passive"))
      (node (ref "FR13") (pin "1") (pinfunction "1_1") (pintype "passive"))
      (node (ref "IC1") (pin "AJ25") (pinfunction "VDD_AFE_AJ25") (pintype "power_in"))
    )
    (net (code "38") (name "Net-(IC1F-VDD_CP_CGEN)") (class "Default")
      (node (ref "C100") (pin "2") (pinfunction "2_2") (pintype "passive"))
      (node (ref "FR14") (pin "1") (pinfunction "1_1") (pintype "passive"))
      (node (ref "IC1") (pin "F20") (pinfunction "VDD_CP_CGEN_F20") (pintype "power_in"))
    )
    (net (code "39") (name "Net-(IC1F-VDD_CP_SXR)") (class "Default")
      (node (ref "C105") (pin "1") (pinfunction "1_1") (pintype "passive"))
      (node (ref "FR9") (pin "1") (pinfunction "1_1") (pintype "passive"))
      (node (ref "IC1") (pin "AL19") (pinfunction "VDD_CP_SXR_AL19") (pintype "power_in"))
    )
    (net (code "40") (name "Net-(IC1F-VDD_CP_SXT)") (class "Default")
      (node (ref "C108") (pin "1") (pinfunction "1_1") (pintype "passive"))
      (node (ref "FR5") (pin "1") (pinfunction "1_1") (pintype "passive"))
      (node (ref "IC1") (pin "J3") (pinfunction "VDD_CP_SXT_J3") (pintype "power_in"))
    )
    (net (code "41") (name "Net-(IC1F-VDD_DIV_CGEN)") (class "Default")
      (node (ref "C99") (pin "1") (pinfunction "1_1") (pintype "passive"))
      (node (ref "FR15") (pin "1") (pinfunction "1_1") (pintype "passive"))
      (node (ref "IC1") (pin "E19") (pinfunction "VDD_DIV_CGEN_E19") (pintype "power_in"))
    )
    (net (code "42") (name "Net-(IC1F-VDD_DIV_SXR)") (class "Default")
      (node (ref "C104") (pin "1") (pinfunction "1_1") (pintype "passive"))
      (node (ref "FR10") (pin "1") (pinfunction "1_1") (pintype "passive"))
      (node (ref "IC1") (pin "AM20") (pinfunction "VDD_DIV_SXR_AM20") (pintype "power_in"))
    )
    (net (code "43") (name "Net-(IC1F-VDD_MXLOBUF_RFE)") (class "Default")
      (node (ref "C116") (pin "1") (pinfunction "1_1") (pintype "passive"))
      (node (ref "FR19") (pin "1") (pinfunction "1_1") (pintype "passive"))
      (node (ref "IC1") (pin "AN17") (pinfunction "VDD_MXLOBUF_RFE_AN17") (pintype "power_in"))
    )
    (net (code "44") (name "Net-(IC1F-VDD_TBB)") (class "Default")
      (node (ref "C96") (pin "1") (pinfunction "1_1") (pintype "passive"))
      (node (ref "FR6") (pin "1") (pinfunction "1_1") (pintype "passive"))
      (node (ref "IC1") (pin "P4") (pinfunction "VDD_TBB_P4") (pintype "power_in"))
    )
    (net (code "45") (name "Net-(IC1F-VDD_TPAD_TRF)") (class "Default")
      (node (ref "C98") (pin "1") (pinfunction "1_1") (pintype "passive"))
      (node (ref "FR16") (pin "1") (pinfunction "1_1") (pintype "passive"))
      (node (ref "IC1") (pin "B16") (pinfunction "VDD_TPAD_TRF_B16") (pintype "power_in"))
    )
    (net (code "46") (name "VCC1P4_LMS1") (class "Default")
      (node (ref "FR18") (pin "2") (pinfunction "2_2") (pintype "passive"))
      (node (ref "FR19") (pin "2") (pinfunction "2_2") (pintype "passive"))
      (node (ref "FR20") (pin "2") (pinfunction "2_2") (pintype "passive"))
      (node (ref "FR21") (pin "2") (pinfunction "2_2") (pintype "passive"))
      (node (ref "FR22") (pin "2") (pinfunction "2_2") (pintype "passive"))
      (node (ref "FR23") (pin "2") (pinfunction "2_2") (pintype "passive"))
      (node (ref "R75") (pin "1") (pinfunction "1_1") (pintype "passive"))
    )
    (net (code "47") (name "VCC1P8_LMS1") (class "Default")
      (node (ref "FR24") (pin "2") (pinfunction "2_2") (pintype "passive"))
      (node (ref "FR25") (pin "1") (pinfunction "1_1") (pintype "passive"))
      (node (ref "FR26") (pin "1") (pinfunction "1_1") (pintype "passive"))
      (node (ref "FR27") (pin "2") (pinfunction "2_2") (pintype "passive"))
      (node (ref "FR28") (pin "2") (pinfunction "2_2") (pintype "passive"))
      (node (ref "FR29") (pin "2") (pinfunction "2_2") (pintype "passive"))
      (node (ref "FR30") (pin "2") (pinfunction "2_2") (pintype "passive"))
      (node (ref "FR31") (pin "2") (pinfunction "2_2") (pintype "passive"))
      (node (ref "R79") (pin "2") (pinfunction "2_2") (pintype "passive"))
      (node (ref "R85") (pin "2") (pinfunction "2_2") (pintype "passive"))
      (node (ref "R86") (pin "1") (pinfunction "1_1") (pintype "passive"))
    )
    (net (code "48") (name "VCC1P25_LMS1") (class "Default")
      (node (ref "FR1") (pin "2") (pinfunction "2_2") (pintype "passive"))
      (node (ref "FR10") (pin "2") (pinfunction "2_2") (pintype "passive"))
      (node (ref "FR11") (pin "2") (pinfunction "2_2") (pintype "passive"))
      (node (ref "FR12") (pin "2") (pinfunction "2_2") (pintype "passive"))
      (node (ref "FR13") (pin "2") (pinfunction "2_2") (pintype "passive"))
      (node (ref "FR14") (pin "2") (pinfunction "2_2") (pintype "passive"))
      (node (ref "FR15") (pin "2") (pinfunction "2_2") (pintype "passive"))
      (node (ref "FR16") (pin "2") (pinfunction "2_2") (pintype "passive"))
      (node (ref "FR17") (pin "2") (pinfunction "2_2") (pintype "passive"))
      (node (ref "FR2") (pin "2") (pinfunction "2_2") (pintype "passive"))
      (node (ref "FR3") (pin "2") (pinfunction "2_2") (pintype "passive"))
      (node (ref "FR4") (pin "2") (pinfunction "2_2") (pintype "passive"))
      (node (ref "FR5") (pin "2") (pinfunction "2_2") (pintype "passive"))
      (node (ref "FR6") (pin "2") (pinfunction "2_2") (pintype "passive"))
      (node (ref "FR7") (pin "2") (pinfunction "2_2") (pintype "passive"))
      (node (ref "FR8") (pin "2") (pinfunction "2_2") (pintype "passive"))
      (node (ref "FR9") (pin "2") (pinfunction "2_2") (pintype "passive"))
      (node (ref "R76") (pin "1") (pinfunction "1_1") (pintype "passive"))
    )
    (net (code "49") (name "VDIO_LMS") (class "Default")
      (node (ref "C118") (pin "2") (pinfunction "2_2") (pintype "passive"))
      (node (ref "R80") (pin "1") (pinfunction "1_1") (pintype "passive"))
      (node (ref "R81") (pin "1") (pinfunction "1_1") (pintype "passive"))
      (node (ref "R82") (pin "1") (pinfunction "1_1") (pintype "passive"))
      (node (ref "R83") (pin "1") (pinfunction "1_1") (pintype "passive"))
      (node (ref "R84") (pin "1") (pinfunction "1_1") (pintype "passive"))
    )
  )
)
